# cpu.net
KiCad netlist of a schematic drawn in EAGLE
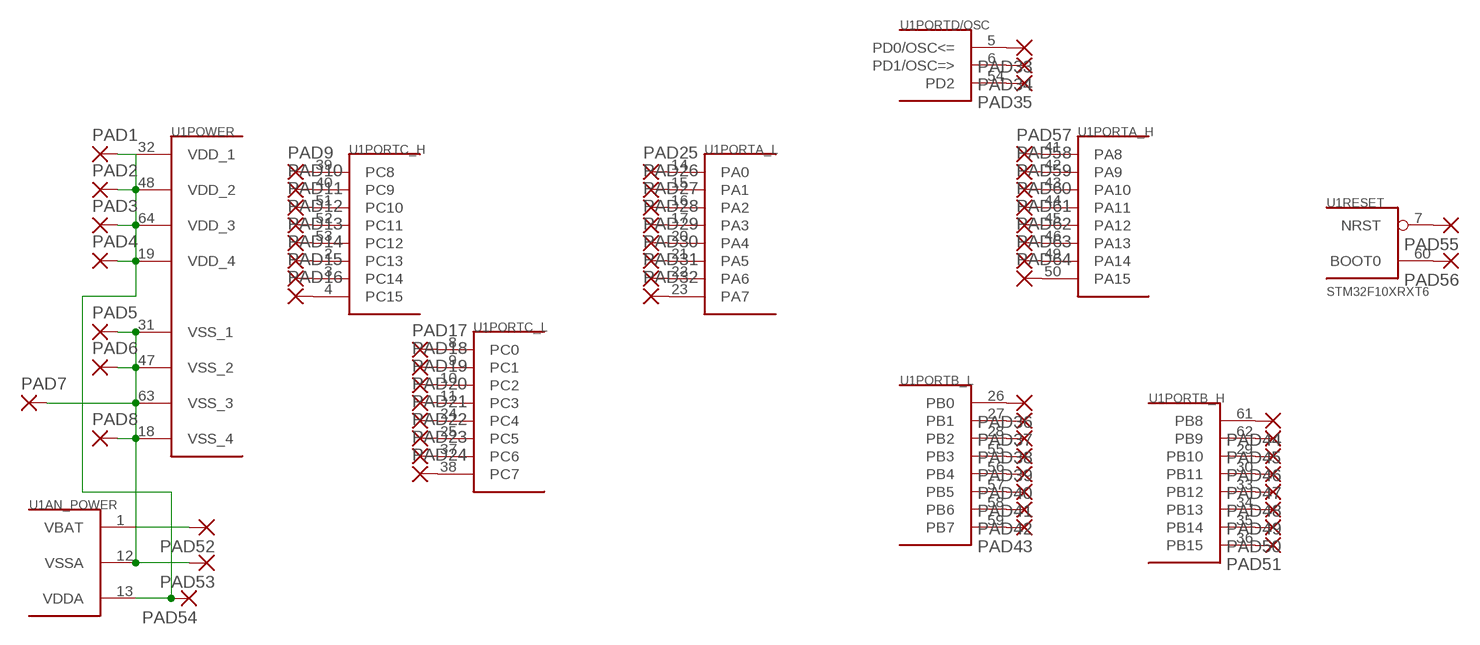
[diagram p0: schematic, sheet 1]

(export (version "E")
  (design (tool "Eeschema 10.0.6"))
  (components
    (comp (ref "PAD1")
      (value "SMD2")
      (footprint "eagle-import:SMD1,27-2,54")
      (libsource (lib "eagle-import") (part "SMD2"))
    )
    (comp (ref "PAD2")
      (value "SMD2")
      (footprint "eagle-import:SMD1,27-2,54")
      (libsource (lib "eagle-import") (part "SMD2"))
    )
    (comp (ref "PAD3")
      (value "SMD2")
      (footprint "eagle-import:SMD1,27-2,54")
      (libsource (lib "eagle-import") (part "SMD2"))
    )
    (comp (ref "PAD4")
      (value "SMD2")
      (footprint "eagle-import:SMD1,27-2,54")
      (libsource (lib "eagle-import") (part "SMD2"))
    )
    (comp (ref "PAD5")
      (value "SMD2")
      (footprint "eagle-import:SMD1,27-2,54")
      (libsource (lib "eagle-import") (part "SMD2"))
    )
    (comp (ref "PAD6")
      (value "SMD2")
      (footprint "eagle-import:SMD1,27-2,54")
      (libsource (lib "eagle-import") (part "SMD2"))
    )
    (comp (ref "PAD7")
      (value "SMD2")
      (footprint "eagle-import:SMD1,27-2,54")
      (libsource (lib "eagle-import") (part "SMD2"))
    )
    (comp (ref "PAD8")
      (value "SMD2")
      (footprint "eagle-import:SMD1,27-2,54")
      (libsource (lib "eagle-import") (part "SMD2"))
    )
    (comp (ref "PAD9")
      (value "SMD2")
      (footprint "eagle-import:SMD1,27-2,54")
      (libsource (lib "eagle-import") (part "SMD2"))
    )
    (comp (ref "PAD10")
      (value "SMD2")
      (footprint "eagle-import:SMD1,27-2,54")
      (libsource (lib "eagle-import") (part "SMD2"))
    )
    (comp (ref "PAD11")
      (value "SMD2")
      (footprint "eagle-import:SMD1,27-2,54")
      (libsource (lib "eagle-import") (part "SMD2"))
    )
    (comp (ref "PAD12")
      (value "SMD2")
      (footprint "eagle-import:SMD1,27-2,54")
      (libsource (lib "eagle-import") (part "SMD2"))
    )
    (comp (ref "PAD13")
      (value "SMD2")
      (footprint "eagle-import:SMD1,27-2,54")
      (libsource (lib "eagle-import") (part "SMD2"))
    )
    (comp (ref "PAD14")
      (value "SMD2")
      (footprint "eagle-import:SMD1,27-2,54")
      (libsource (lib "eagle-import") (part "SMD2"))
    )
    (comp (ref "PAD15")
      (value "SMD2")
      (footprint "eagle-import:SMD1,27-2,54")
      (libsource (lib "eagle-import") (part "SMD2"))
    )
    (comp (ref "PAD16")
      (value "SMD2")
      (footprint "eagle-import:SMD1,27-2,54")
      (libsource (lib "eagle-import") (part "SMD2"))
    )
    (comp (ref "PAD17")
      (value "SMD2")
      (footprint "eagle-import:SMD1,27-2,54")
      (libsource (lib "eagle-import") (part "SMD2"))
    )
    (comp (ref "PAD18")
      (value "SMD2")
      (footprint "eagle-import:SMD1,27-2,54")
      (libsource (lib "eagle-import") (part "SMD2"))
    )
    (comp (ref "PAD19")
      (value "SMD2")
      (footprint "eagle-import:SMD1,27-2,54")
      (libsource (lib "eagle-import") (part "SMD2"))
    )
    (comp (ref "PAD20")
      (value "SMD2")
      (footprint "eagle-import:SMD1,27-2,54")
      (libsource (lib "eagle-import") (part "SMD2"))
    )
    (comp (ref "PAD21")
      (value "SMD2")
      (footprint "eagle-import:SMD1,27-2,54")
      (libsource (lib "eagle-import") (part "SMD2"))
    )
    (comp (ref "PAD22")
      (value "SMD2")
      (footprint "eagle-import:SMD1,27-2,54")
      (libsource (lib "eagle-import") (part "SMD2"))
    )
    (comp (ref "PAD23")
      (value "SMD2")
      (footprint "eagle-import:SMD1,27-2,54")
      (libsource (lib "eagle-import") (part "SMD2"))
    )
    (comp (ref "PAD24")
      (value "SMD2")
      (footprint "eagle-import:SMD1,27-2,54")
      (libsource (lib "eagle-import") (part "SMD2"))
    )
    (comp (ref "PAD25")
      (value "SMD2")
      (footprint "eagle-import:SMD1,27-2,54")
      (libsource (lib "eagle-import") (part "SMD2"))
    )
    (comp (ref "PAD26")
      (value "SMD2")
      (footprint "eagle-import:SMD1,27-2,54")
      (libsource (lib "eagle-import") (part "SMD2"))
    )
    (comp (ref "PAD27")
      (value "SMD2")
      (footprint "eagle-import:SMD1,27-2,54")
      (libsource (lib "eagle-import") (part "SMD2"))
    )
    (comp (ref "PAD28")
      (value "SMD2")
      (footprint "eagle-import:SMD1,27-2,54")
      (libsource (lib "eagle-import") (part "SMD2"))
    )
    (comp (ref "PAD29")
      (value "SMD2")
      (footprint "eagle-import:SMD1,27-2,54")
      (libsource (lib "eagle-import") (part "SMD2"))
    )
    (comp (ref "PAD30")
      (value "SMD2")
      (footprint "eagle-import:SMD1,27-2,54")
      (libsource (lib "eagle-import") (part "SMD2"))
    )
    (comp (ref "PAD31")
      (value "SMD2")
      (footprint "eagle-import:SMD1,27-2,54")
      (libsource (lib "eagle-import") (part "SMD2"))
    )
    (comp (ref "PAD32")
      (value "SMD2")
      (footprint "eagle-import:SMD1,27-2,54")
      (libsource (lib "eagle-import") (part "SMD2"))
    )
    (comp (ref "PAD33")
      (value "SMD2")
      (footprint "eagle-import:SMD1,27-2,54")
      (libsource (lib "eagle-import") (part "SMD2"))
    )
    (comp (ref "PAD34")
      (value "SMD2")
      (footprint "eagle-import:SMD1,27-2,54")
      (libsource (lib "eagle-import") (part "SMD2"))
    )
    (comp (ref "PAD35")
      (value "SMD2")
      (footprint "eagle-import:SMD1,27-2,54")
      (libsource (lib "eagle-import") (part "SMD2"))
    )
    (comp (ref "PAD36")
      (value "SMD2")
      (footprint "eagle-import:SMD1,27-2,54")
      (libsource (lib "eagle-import") (part "SMD2"))
    )
    (comp (ref "PAD37")
      (value "SMD2")
      (footprint "eagle-import:SMD1,27-2,54")
      (libsource (lib "eagle-import") (part "SMD2"))
    )
    (comp (ref "PAD38")
      (value "SMD2")
      (footprint "eagle-import:SMD1,27-2,54")
      (libsource (lib "eagle-import") (part "SMD2"))
    )
    (comp (ref "PAD39")
      (value "SMD2")
      (footprint "eagle-import:SMD1,27-2,54")
      (libsource (lib "eagle-import") (part "SMD2"))
    )
    (comp (ref "PAD40")
      (value "SMD2")
      (footprint "eagle-import:SMD1,27-2,54")
      (libsource (lib "eagle-import") (part "SMD2"))
    )
    (comp (ref "PAD41")
      (value "SMD2")
      (footprint "eagle-import:SMD1,27-2,54")
      (libsource (lib "eagle-import") (part "SMD2"))
    )
    (comp (ref "PAD42")
      (value "SMD2")
      (footprint "eagle-import:SMD1,27-2,54")
      (libsource (lib "eagle-import") (part "SMD2"))
    )
    (comp (ref "PAD43")
      (value "SMD2")
      (footprint "eagle-import:SMD1,27-2,54")
      (libsource (lib "eagle-import") (part "SMD2"))
    )
    (comp (ref "PAD44")
      (value "SMD2")
      (footprint "eagle-import:SMD1,27-2,54")
      (libsource (lib "eagle-import") (part "SMD2"))
    )
    (comp (ref "PAD45")
      (value "SMD2")
      (footprint "eagle-import:SMD1,27-2,54")
      (libsource (lib "eagle-import") (part "SMD2"))
    )
    (comp (ref "PAD46")
      (value "SMD2")
      (footprint "eagle-import:SMD1,27-2,54")
      (libsource (lib "eagle-import") (part "SMD2"))
    )
    (comp (ref "PAD47")
      (value "SMD2")
      (footprint "eagle-import:SMD1,27-2,54")
      (libsource (lib "eagle-import") (part "SMD2"))
    )
    (comp (ref "PAD48")
      (value "SMD2")
      (footprint "eagle-import:SMD1,27-2,54")
      (libsource (lib "eagle-import") (part "SMD2"))
    )
    (comp (ref "PAD49")
      (value "SMD2")
      (footprint "eagle-import:SMD1,27-2,54")
      (libsource (lib "eagle-import") (part "SMD2"))
    )
    (comp (ref "PAD50")
      (value "SMD2")
      (footprint "eagle-import:SMD1,27-2,54")
      (libsource (lib "eagle-import") (part "SMD2"))
    )
    (comp (ref "PAD51")
      (value "SMD2")
      (footprint "eagle-import:SMD1,27-2,54")
      (libsource (lib "eagle-import") (part "SMD2"))
    )
    (comp (ref "PAD52")
      (value "SMD2")
      (footprint "eagle-import:SMD1,27-2,54")
      (libsource (lib "eagle-import") (part "SMD2"))
    )
    (comp (ref "PAD53")
      (value "SMD2")
      (footprint "eagle-import:SMD1,27-2,54")
      (libsource (lib "eagle-import") (part "SMD2"))
    )
    (comp (ref "PAD54")
      (value "SMD2")
      (footprint "eagle-import:SMD1,27-2,54")
      (libsource (lib "eagle-import") (part "SMD2"))
    )
    (comp (ref "PAD55")
      (value "SMD2")
      (footprint "eagle-import:SMD1,27-2,54")
      (libsource (lib "eagle-import") (part "SMD2"))
    )
    (comp (ref "PAD56")
      (value "SMD2")
      (footprint "eagle-import:SMD1,27-2,54")
      (libsource (lib "eagle-import") (part "SMD2"))
    )
    (comp (ref "PAD57")
      (value "SMD2")
      (footprint "eagle-import:SMD1,27-2,54")
      (libsource (lib "eagle-import") (part "SMD2"))
    )
    (comp (ref "PAD58")
      (value "SMD2")
      (footprint "eagle-import:SMD1,27-2,54")
      (libsource (lib "eagle-import") (part "SMD2"))
    )
    (comp (ref "PAD59")
      (value "SMD2")
      (footprint "eagle-import:SMD1,27-2,54")
      (libsource (lib "eagle-import") (part "SMD2"))
    )
    (comp (ref "PAD60")
      (value "SMD2")
      (footprint "eagle-import:SMD1,27-2,54")
      (libsource (lib "eagle-import") (part "SMD2"))
    )
    (comp (ref "PAD61")
      (value "SMD2")
      (footprint "eagle-import:SMD1,27-2,54")
      (libsource (lib "eagle-import") (part "SMD2"))
    )
    (comp (ref "PAD62")
      (value "SMD2")
      (footprint "eagle-import:SMD1,27-2,54")
      (libsource (lib "eagle-import") (part "SMD2"))
    )
    (comp (ref "PAD63")
      (value "SMD2")
      (footprint "eagle-import:SMD1,27-2,54")
      (libsource (lib "eagle-import") (part "SMD2"))
    )
    (comp (ref "PAD64")
      (value "SMD2")
      (footprint "eagle-import:SMD1,27-2,54")
      (libsource (lib "eagle-import") (part "SMD2"))
    )
    (comp (ref "U1")
      (value "STM32F10XRXT6")
      (footprint "eagle-import:TQFP64")
      (libsource (lib "eagle-import") (part "STM32F10XRXT6"))
    )
  )
  (nets
    (net (code "1") (name "Net-(PAD1-P)") (class "Default")
      (node (ref "PAD1") (pin "1") (pinfunction "P_1") (pintype "passive"))
      (node (ref "PAD2") (pin "1") (pinfunction "P_1") (pintype "passive"))
      (node (ref "PAD3") (pin "1") (pinfunction "P_1") (pintype "passive"))
      (node (ref "PAD4") (pin "1") (pinfunction "P_1") (pintype "passive"))
      (node (ref "PAD54") (pin "1") (pinfunction "P_1") (pintype "passive"))
      (node (ref "U1") (pin "13") (pinfunction "VDDA_13") (pintype "power_in"))
      (node (ref "U1") (pin "19") (pinfunction "VDD_4_19") (pintype "power_in"))
      (node (ref "U1") (pin "32") (pinfunction "VDD_1_32") (pintype "power_in"))
      (node (ref "U1") (pin "48") (pinfunction "VDD_2_48") (pintype "power_in"))
      (node (ref "U1") (pin "64") (pinfunction "VDD_3_64") (pintype "power_in"))
    )
    (net (code "2") (name "Net-(PAD5-P)") (class "Default")
      (node (ref "PAD5") (pin "1") (pinfunction "P_1") (pintype "passive"))
      (node (ref "PAD53") (pin "1") (pinfunction "P_1") (pintype "passive"))
      (node (ref "PAD6") (pin "1") (pinfunction "P_1") (pintype "passive"))
      (node (ref "PAD7") (pin "1") (pinfunction "P_1") (pintype "passive"))
      (node (ref "PAD8") (pin "1") (pinfunction "P_1") (pintype "passive"))
      (node (ref "U1") (pin "12") (pinfunction "VSSA_12") (pintype "power_in"))
      (node (ref "U1") (pin "18") (pinfunction "VSS_4_18") (pintype "power_in"))
      (node (ref "U1") (pin "31") (pinfunction "VSS_1_31") (pintype "power_in"))
      (node (ref "U1") (pin "47") (pinfunction "VSS_2_47") (pintype "power_in"))
      (node (ref "U1") (pin "63") (pinfunction "VSS_3_63") (pintype "power_in"))
    )
    (net (code "3") (name "Net-(PAD9-P)") (class "Default")
      (node (ref "PAD9") (pin "1") (pinfunction "P_1") (pintype "passive"))
      (node (ref "U1") (pin "39") (pinfunction "PC8_39") (pintype "bidirectional"))
    )
    (net (code "4") (name "Net-(PAD10-P)") (class "Default")
      (node (ref "PAD10") (pin "1") (pinfunction "P_1") (pintype "passive"))
      (node (ref "U1") (pin "40") (pinfunction "PC9_40") (pintype "bidirectional"))
    )
    (net (code "5") (name "Net-(PAD11-P)") (class "Default")
      (node (ref "PAD11") (pin "1") (pinfunction "P_1") (pintype "passive"))
      (node (ref "U1") (pin "51") (pinfunction "PC10_51") (pintype "bidirectional"))
    )
    (net (code "6") (name "Net-(PAD12-P)") (class "Default")
      (node (ref "PAD12") (pin "1") (pinfunction "P_1") (pintype "passive"))
      (node (ref "U1") (pin "52") (pinfunction "PC11_52") (pintype "bidirectional"))
    )
    (net (code "7") (name "Net-(PAD13-P)") (class "Default")
      (node (ref "PAD13") (pin "1") (pinfunction "P_1") (pintype "passive"))
      (node (ref "U1") (pin "53") (pinfunction "PC12_53") (pintype "bidirectional"))
    )
    (net (code "8") (name "Net-(PAD14-P)") (class "Default")
      (node (ref "PAD14") (pin "1") (pinfunction "P_1") (pintype "passive"))
      (node (ref "U1") (pin "2") (pinfunction "PC13_2") (pintype "bidirectional"))
    )
    (net (code "9") (name "Net-(PAD15-P)") (class "Default")
      (node (ref "PAD15") (pin "1") (pinfunction "P_1") (pintype "passive"))
      (node (ref "U1") (pin "3") (pinfunction "PC14_3") (pintype "bidirectional"))
    )
    (net (code "10") (name "Net-(PAD16-P)") (class "Default")
      (node (ref "PAD16") (pin "1") (pinfunction "P_1") (pintype "passive"))
      (node (ref "U1") (pin "4") (pinfunction "PC15_4") (pintype "bidirectional"))
    )
    (net (code "11") (name "Net-(PAD17-P)") (class "Default")
      (node (ref "PAD17") (pin "1") (pinfunction "P_1") (pintype "passive"))
      (node (ref "U1") (pin "8") (pinfunction "PC0_8") (pintype "bidirectional"))
    )
    (net (code "12") (name "Net-(PAD18-P)") (class "Default")
      (node (ref "PAD18") (pin "1") (pinfunction "P_1") (pintype "passive"))
      (node (ref "U1") (pin "9") (pinfunction "PC1_9") (pintype "bidirectional"))
    )
    (net (code "13") (name "Net-(PAD19-P)") (class "Default")
      (node (ref "PAD19") (pin "1") (pinfunction "P_1") (pintype "passive"))
      (node (ref "U1") (pin "10") (pinfunction "PC2_10") (pintype "bidirectional"))
    )
    (net (code "14") (name "Net-(PAD20-P)") (class "Default")
      (node (ref "PAD20") (pin "1") (pinfunction "P_1") (pintype "passive"))
      (node (ref "U1") (pin "11") (pinfunction "PC3_11") (pintype "bidirectional"))
    )
    (net (code "15") (name "Net-(PAD21-P)") (class "Default")
      (node (ref "PAD21") (pin "1") (pinfunction "P_1") (pintype "passive"))
      (node (ref "U1") (pin "24") (pinfunction "PC4_24") (pintype "bidirectional"))
    )
    (net (code "16") (name "Net-(PAD22-P)") (class "Default")
      (node (ref "PAD22") (pin "1") (pinfunction "P_1") (pintype "passive"))
      (node (ref "U1") (pin "25") (pinfunction "PC5_25") (pintype "bidirectional"))
    )
    (net (code "17") (name "Net-(PAD23-P)") (class "Default")
      (node (ref "PAD23") (pin "1") (pinfunction "P_1") (pintype "passive"))
      (node (ref "U1") (pin "37") (pinfunction "PC6_37") (pintype "bidirectional"))
    )
    (net (code "18") (name "Net-(PAD24-P)") (class "Default")
      (node (ref "PAD24") (pin "1") (pinfunction "P_1") (pintype "passive"))
      (node (ref "U1") (pin "38") (pinfunction "PC7_38") (pintype "bidirectional"))
    )
    (net (code "19") (name "Net-(PAD25-P)") (class "Default")
      (node (ref "PAD25") (pin "1") (pinfunction "P_1") (pintype "passive"))
      (node (ref "U1") (pin "14") (pinfunction "PA0_14") (pintype "bidirectional"))
    )
    (net (code "20") (name "Net-(PAD26-P)") (class "Default")
      (node (ref "PAD26") (pin "1") (pinfunction "P_1") (pintype "passive"))
      (node (ref "U1") (pin "15") (pinfunction "PA1_15") (pintype "bidirectional"))
    )
    (net (code "21") (name "Net-(PAD27-P)") (class "Default")
      (node (ref "PAD27") (pin "1") (pinfunction "P_1") (pintype "passive"))
      (node (ref "U1") (pin "16") (pinfunction "PA2_16") (pintype "bidirectional"))
    )
    (net (code "22") (name "Net-(PAD28-P)") (class "Default")
      (node (ref "PAD28") (pin "1") (pinfunction "P_1") (pintype "passive"))
      (node (ref "U1") (pin "17") (pinfunction "PA3_17") (pintype "bidirectional"))
    )
    (net (code "23") (name "Net-(PAD29-P)") (class "Default")
      (node (ref "PAD29") (pin "1") (pinfunction "P_1") (pintype "passive"))
      (node (ref "U1") (pin "20") (pinfunction "PA4_20") (pintype "bidirectional"))
    )
    (net (code "24") (name "Net-(PAD30-P)") (class "Default")
      (node (ref "PAD30") (pin "1") (pinfunction "P_1") (pintype "passive"))
      (node (ref "U1") (pin "21") (pinfunction "PA5_21") (pintype "bidirectional"))
    )
    (net (code "25") (name "Net-(PAD31-P)") (class "Default")
      (node (ref "PAD31") (pin "1") (pinfunction "P_1") (pintype "passive"))
      (node (ref "U1") (pin "22") (pinfunction "PA6_22") (pintype "bidirectional"))
    )
    (net (code "26") (name "Net-(PAD32-P)") (class "Default")
      (node (ref "PAD32") (pin "1") (pinfunction "P_1") (pintype "passive"))
      (node (ref "U1") (pin "23") (pinfunction "PA7_23") (pintype "bidirectional"))
    )
    (net (code "27") (name "Net-(PAD33-P)") (class "Default")
      (node (ref "PAD33") (pin "1") (pinfunction "P_1") (pintype "passive"))
      (node (ref "U1") (pin "5") (pinfunction "PD0/OSC<=_5") (pintype "bidirectional"))
    )
    (net (code "28") (name "Net-(PAD34-P)") (class "Default")
      (node (ref "PAD34") (pin "1") (pinfunction "P_1") (pintype "passive"))
      (node (ref "U1") (pin "6") (pinfunction "PD1/OSC=>_6") (pintype "bidirectional"))
    )
    (net (code "29") (name "Net-(PAD35-P)") (class "Default")
      (node (ref "PAD35") (pin "1") (pinfunction "P_1") (pintype "passive"))
      (node (ref "U1") (pin "54") (pinfunction "PD2_54") (pintype "bidirectional"))
    )
    (net (code "30") (name "Net-(PAD36-P)") (class "Default")
      (node (ref "PAD36") (pin "1") (pinfunction "P_1") (pintype "passive"))
      (node (ref "U1") (pin "26") (pinfunction "PB0_26") (pintype "bidirectional"))
    )
    (net (code "31") (name "Net-(PAD37-P)") (class "Default")
      (node (ref "PAD37") (pin "1") (pinfunction "P_1") (pintype "passive"))
      (node (ref "U1") (pin "27") (pinfunction "PB1_27") (pintype "bidirectional"))
    )
    (net (code "32") (name "Net-(PAD38-P)") (class "Default")
      (node (ref "PAD38") (pin "1") (pinfunction "P_1") (pintype "passive"))
      (node (ref "U1") (pin "28") (pinfunction "PB2_28") (pintype "bidirectional"))
    )
    (net (code "33") (name "Net-(PAD39-P)") (class "Default")
      (node (ref "PAD39") (pin "1") (pinfunction "P_1") (pintype "passive"))
      (node (ref "U1") (pin "55") (pinfunction "PB3_55") (pintype "bidirectional"))
    )
    (net (code "34") (name "Net-(PAD40-P)") (class "Default")
      (node (ref "PAD40") (pin "1") (pinfunction "P_1") (pintype "passive"))
      (node (ref "U1") (pin "56") (pinfunction "PB4_56") (pintype "bidirectional"))
    )
    (net (code "35") (name "Net-(PAD41-P)") (class "Default")
      (node (ref "PAD41") (pin "1") (pinfunction "P_1") (pintype "passive"))
      (node (ref "U1") (pin "57") (pinfunction "PB5_57") (pintype "bidirectional"))
    )
    (net (code "36") (name "Net-(PAD42-P)") (class "Default")
      (node (ref "PAD42") (pin "1") (pinfunction "P_1") (pintype "passive"))
      (node (ref "U1") (pin "58") (pinfunction "PB6_58") (pintype "bidirectional"))
    )
    (net (code "37") (name "Net-(PAD43-P)") (class "Default")
      (node (ref "PAD43") (pin "1") (pinfunction "P_1") (pintype "passive"))
      (node (ref "U1") (pin "59") (pinfunction "PB7_59") (pintype "bidirectional"))
    )
    (net (code "38") (name "Net-(PAD44-P)") (class "Default")
      (node (ref "PAD44") (pin "1") (pinfunction "P_1") (pintype "passive"))
      (node (ref "U1") (pin "61") (pinfunction "PB8_61") (pintype "bidirectional"))
    )
    (net (code "39") (name "Net-(PAD45-P)") (class "Default")
      (node (ref "PAD45") (pin "1") (pinfunction "P_1") (pintype "passive"))
      (node (ref "U1") (pin "62") (pinfunction "PB9_62") (pintype "bidirectional"))
    )
    (net (code "40") (name "Net-(PAD46-P)") (class "Default")
      (node (ref "PAD46") (pin "1") (pinfunction "P_1") (pintype "passive"))
      (node (ref "U1") (pin "29") (pinfunction "PB10_29") (pintype "bidirectional"))
    )
    (net (code "41") (name "Net-(PAD47-P)") (class "Default")
      (node (ref "PAD47") (pin "1") (pinfunction "P_1") (pintype "passive"))
      (node (ref "U1") (pin "30") (pinfunction "PB11_30") (pintype "bidirectional"))
    )
    (net (code "42") (name "Net-(PAD48-P)") (class "Default")
      (node (ref "PAD48") (pin "1") (pinfunction "P_1") (pintype "passive"))
      (node (ref "U1") (pin "33") (pinfunction "PB12_33") (pintype "bidirectional"))
    )
    (net (code "43") (name "Net-(PAD49-P)") (class "Default")
      (node (ref "PAD49") (pin "1") (pinfunction "P_1") (pintype "passive"))
      (node (ref "U1") (pin "34") (pinfunction "PB13_34") (pintype "bidirectional"))
    )
    (net (code "44") (name "Net-(PAD50-P)") (class "Default")
      (node (ref "PAD50") (pin "1") (pinfunction "P_1") (pintype "passive"))
      (node (ref "U1") (pin "35") (pinfunction "PB14_35") (pintype "bidirectional"))
    )
    (net (code "45") (name "Net-(PAD51-P)") (class "Default")
      (node (ref "PAD51") (pin "1") (pinfunction "P_1") (pintype "passive"))
      (node (ref "U1") (pin "36") (pinfunction "PB15_36") (pintype "bidirectional"))
    )
    (net (code "46") (name "Net-(PAD52-P)") (class "Default")
      (node (ref "PAD52") (pin "1") (pinfunction "P_1") (pintype "passive"))
      (node (ref "U1") (pin "1") (pinfunction "VBAT_1") (pintype "power_in"))
    )
    (net (code "47") (name "Net-(PAD55-P)") (class "Default")
      (node (ref "PAD55") (pin "1") (pinfunction "P_1") (pintype "passive"))
      (node (ref "U1") (pin "7") (pinfunction "NRST_7") (pintype "input"))
    )
    (net (code "48") (name "Net-(PAD56-P)") (class "Default")
      (node (ref "PAD56") (pin "1") (pinfunction "P_1") (pintype "passive"))
      (node (ref "U1") (pin "60") (pinfunction "BOOT0_60") (pintype "input"))
    )
    (net (code "49") (name "Net-(PAD57-P)") (class "Default")
      (node (ref "PAD57") (pin "1") (pinfunction "P_1") (pintype "passive"))
      (node (ref "U1") (pin "41") (pinfunction "PA8_41") (pintype "bidirectional"))
    )
    (net (code "50") (name "Net-(PAD58-P)") (class "Default")
      (node (ref "PAD58") (pin "1") (pinfunction "P_1") (pintype "passive"))
      (node (ref "U1") (pin "42") (pinfunction "PA9_42") (pintype "bidirectional"))
    )
    (net (code "51") (name "Net-(PAD59-P)") (class "Default")
      (node (ref "PAD59") (pin "1") (pinfunction "P_1") (pintype "passive"))
      (node (ref "U1") (pin "43") (pinfunction "PA10_43") (pintype "bidirectional"))
    )
    (net (code "52") (name "Net-(PAD60-P)") (class "Default")
      (node (ref "PAD60") (pin "1") (pinfunction "P_1") (pintype "passive"))
      (node (ref "U1") (pin "44") (pinfunction "PA11_44") (pintype "bidirectional"))
    )
    (net (code "53") (name "Net-(PAD61-P)") (class "Default")
      (node (ref "PAD61") (pin "1") (pinfunction "P_1") (pintype "passive"))
      (node (ref "U1") (pin "45") (pinfunction "PA12_45") (pintype "bidirectional"))
    )
    (net (code "54") (name "Net-(PAD62-P)") (class "Default")
      (node (ref "PAD62") (pin "1") (pinfunction "P_1") (pintype "passive"))
      (node (ref "U1") (pin "46") (pinfunction "PA13_46") (pintype "bidirectional"))
    )
    (net (code "55") (name "Net-(PAD63-P)") (class "Default")
      (node (ref "PAD63") (pin "1") (pinfunction "P_1") (pintype "passive"))
      (node (ref "U1") (pin "49") (pinfunction "PA14_49") (pintype "bidirectional"))
    )
    (net (code "56") (name "Net-(PAD64-P)") (class "Default")
      (node (ref "PAD64") (pin "1") (pinfunction "P_1") (pintype "passive"))
      (node (ref "U1") (pin "50") (pinfunction "PA15_50") (pintype "bidirectional"))
    )
  )
)
